# Power_supply.net
KiCad netlist of a schematic drawn in Altium Designer
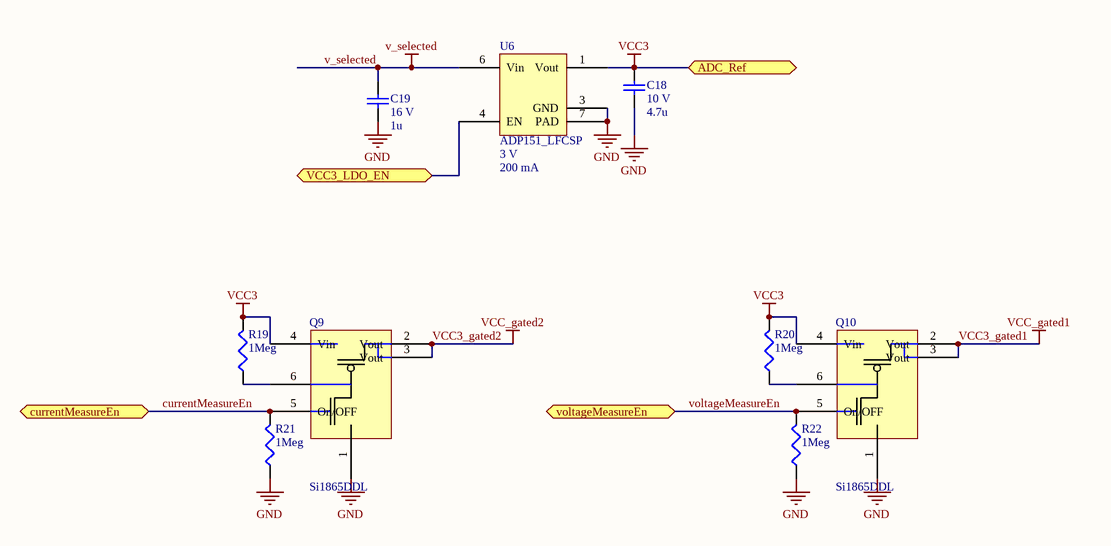
[diagram p0: Power_supply.SchDoc]

(export (version "E")
  (design (tool "Eeschema 10.0.6"))
  (components
    (comp (ref "C18")
      (value "4.7u")
      (footprint "0603")
      (description "4.7µF ±10% 10V Ceramic Capacitor X5R 0603")
      (fields
        (field (name "TOLERANCE") "10%")
        (field (name "VOLTAGE RATED") "10 V")
        (field (name "MANUFACTURER PART NUMBER") "CGB3B1X5R1A475K055AC")
      )
      (libsource (lib "capacitors") (part "CGB3B1X5R1A475K055AC"))
    )
    (comp (ref "C19")
      (value "1u")
      (footprint "0402")
      (description "1µF ±10% 16V Ceramic Capacitor X6S 0402")
      (fields
        (field (name "VOLTAGE RATED") "16 V")
        (field (name "TOLERANCE") "10%")
        (field (name "MANUFACTURER PART NUMBER") "C1005X6S1C105K050BC")
      )
      (libsource (lib "capacitors") (part "C1005X6S1C105K050BC"))
    )
    (comp (ref "Q9")
      (value "Si1865DDL")
      (footprint "SC70-6")
      (description "Load Switch with Level-Shift")
      (libsource (lib "load switch") (part "Si1865DDL"))
    )
    (comp (ref "Q10")
      (value "Si1865DDL")
      (footprint "SC70-6")
      (description "Load Switch with Level-Shift")
      (libsource (lib "load switch") (part "Si1865DDL"))
    )
    (comp (ref "R19")
      (value "1Meg")
      (footprint "0402")
      (description "RES SMD 1M OHM 1% 1/16W 0402")
      (fields (field (name "TOLERANCE") "1%") (field (name "POWER") "1/16 W"))
      (libsource (lib "resistors") (part "CRCW04021M00FKED"))
    )
    (comp (ref "R20")
      (value "1Meg")
      (footprint "0402")
      (description "RES SMD 1M OHM 1% 1/16W 0402")
      (fields (field (name "TOLERANCE") "1%") (field (name "POWER") "1/16 W"))
      (libsource (lib "resistors") (part "CRCW04021M00FKED"))
    )
    (comp (ref "R21")
      (value "1Meg")
      (footprint "0402")
      (description "RES SMD 1M OHM 1% 1/16W 0402")
      (fields (field (name "TOLERANCE") "1%") (field (name "POWER") "1/16 W"))
      (libsource (lib "resistors") (part "CRCW04021M00FKED"))
    )
    (comp (ref "R22")
      (value "1Meg")
      (footprint "0402")
      (description "RES SMD 1M OHM 1% 1/16W 0402")
      (fields (field (name "TOLERANCE") "1%") (field (name "POWER") "1/16 W"))
      (libsource (lib "resistors") (part "CRCW04021M00FKED"))
    )
    (comp (ref "U6")
      (value "ADP151_LFCSP")
      (footprint "CP-6-3")
      (description "Ultralow Noise, 200 mA,  CMOS Linear Regulator")
      (fields (field (name "VOLTAGE") "3 V") (field (name "CURRENT") "200 mA"))
      (libsource (lib "voltage regulator") (part "ADP151_LFCSP"))
    )
  )
  (nets
    (net (code "1") (name "/VCC3_LDO_EN") (class "Default")
      (node (ref "U6") (pin "4") (pinfunction "EN_4") (pintype "passive"))
    )
    (net (code "2") (name "/currentMeasureEn") (class "Default")
      (node (ref "Q9") (pin "5") (pinfunction "On/OFF_5") (pintype "passive"))
      (node (ref "R21") (pin "1") (pintype "passive"))
    )
    (net (code "3") (name "/voltageMeasureEn") (class "Default")
      (node (ref "Q10") (pin "5") (pinfunction "On/OFF_5") (pintype "passive"))
      (node (ref "R22") (pin "1") (pintype "passive"))
    )
    (net (code "4") (name "GND") (class "Default")
      (node (ref "C18") (pin "2") (pintype "passive"))
      (node (ref "C19") (pin "2") (pintype "passive"))
      (node (ref "Q10") (pin "1") (pinfunction "S1_1") (pintype "passive"))
      (node (ref "Q9") (pin "1") (pinfunction "S1_1") (pintype "passive"))
      (node (ref "R21") (pin "2") (pintype "passive"))
      (node (ref "R22") (pin "2") (pintype "passive"))
      (node (ref "U6") (pin "3") (pinfunction "GND_3") (pintype "passive"))
      (node (ref "U6") (pin "7") (pinfunction "PAD_7") (pintype "passive"))
    )
    (net (code "5") (name "Net-(Q9-D1)") (class "Default")
      (node (ref "Q9") (pin "6") (pinfunction "D1_6") (pintype "passive"))
      (node (ref "R19") (pin "2") (pintype "passive"))
    )
    (net (code "6") (name "Net-(Q10-D1)") (class "Default")
      (node (ref "Q10") (pin "6") (pinfunction "D1_6") (pintype "passive"))
      (node (ref "R20") (pin "2") (pintype "passive"))
    )
    (net (code "7") (name "VCC3") (class "Default")
      (node (ref "C18") (pin "1") (pintype "passive"))
      (node (ref "Q10") (pin "4") (pinfunction "Vin_4") (pintype "passive"))
      (node (ref "Q9") (pin "4") (pinfunction "Vin_4") (pintype "passive"))
      (node (ref "R19") (pin "1") (pintype "passive"))
      (node (ref "R20") (pin "1") (pintype "passive"))
      (node (ref "U6") (pin "1") (pinfunction "Vout_1") (pintype "passive"))
    )
    (net (code "8") (name "VCC_gated1") (class "Default")
      (node (ref "Q10") (pin "2") (pinfunction "Vout_2") (pintype "passive"))
      (node (ref "Q10") (pin "3") (pinfunction "Vout_3") (pintype "passive"))
    )
    (net (code "9") (name "VCC_gated2") (class "Default")
      (node (ref "Q9") (pin "2") (pinfunction "Vout_2") (pintype "passive"))
      (node (ref "Q9") (pin "3") (pinfunction "Vout_3") (pintype "passive"))
    )
    (net (code "10") (name "v_selected") (class "Default")
      (node (ref "C19") (pin "1") (pintype "passive"))
      (node (ref "U6") (pin "6") (pinfunction "Vin_6") (pintype "passive"))
    )
  )
)
